# Sheet1.net
KiCad netlist of a schematic drawn in Altium Designer
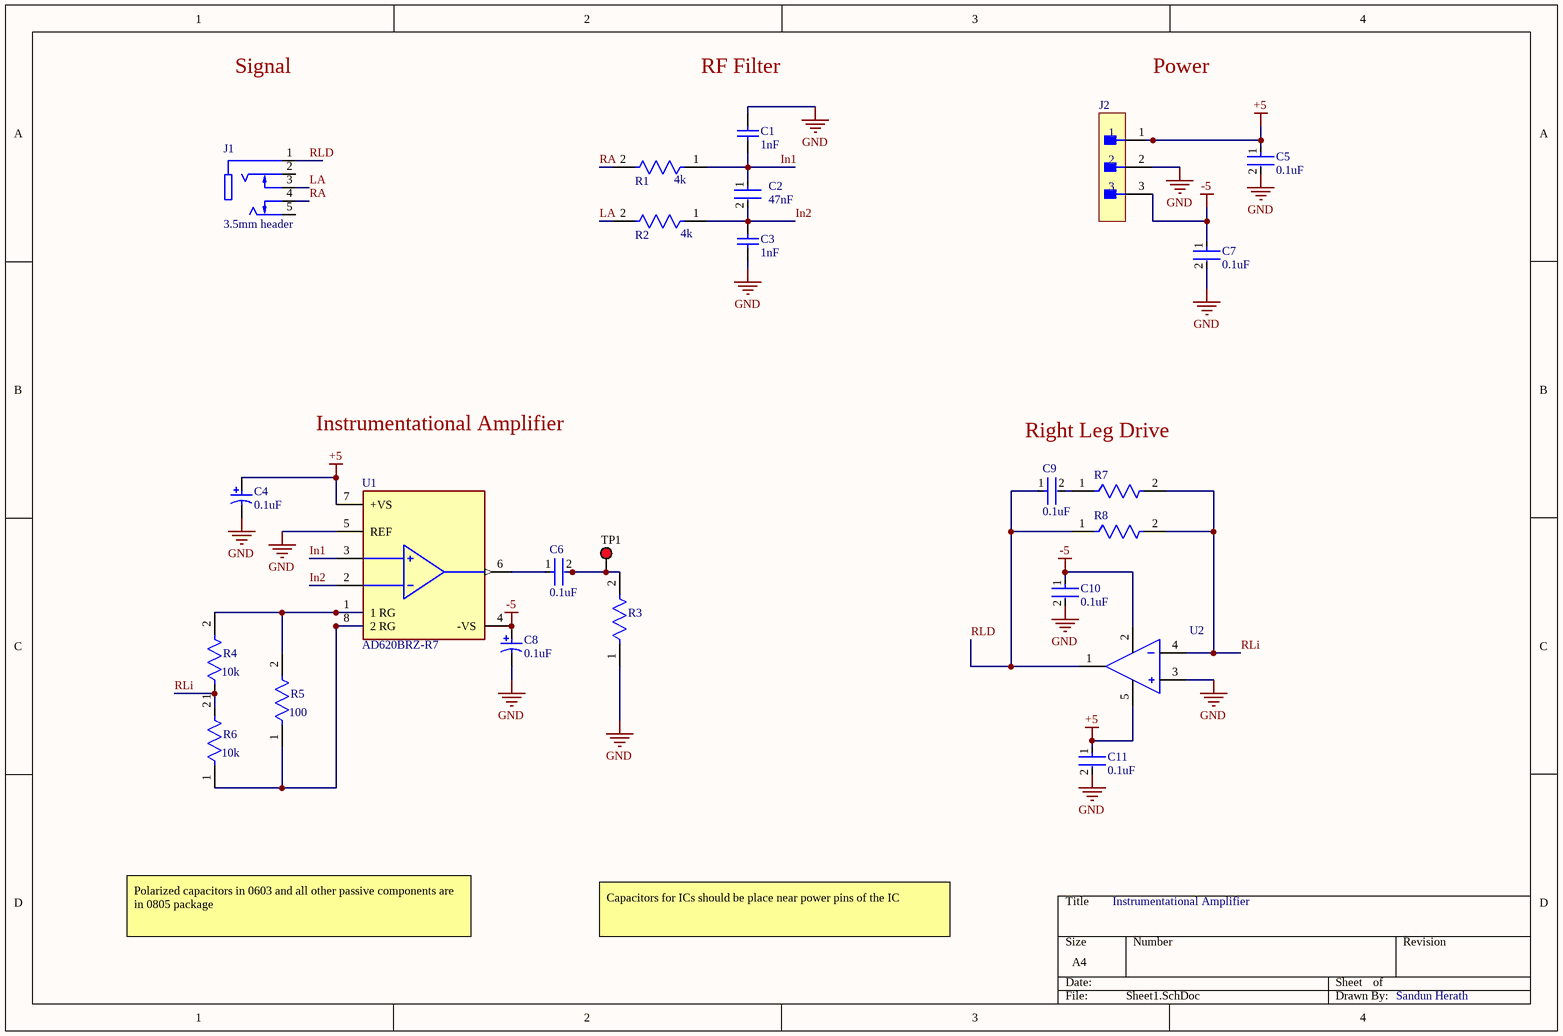
[diagram p0: Sheet1.SchDoc]

(export (version "E")
  (design (tool "Eeschema 10.0.6"))
  (components
    (comp (ref "C1")
      (value "1nF")
      (footprint "CAPC0805(2012)145_L")
      (description "CAP 1nF 50V ±5% 0805 (2012 Metric) Thickness 1.45mm SMD")
      (fields (field (name "TOLERANCE") "Â±5%"))
      (libsource (lib "Altium Content Vault") (part "CAP"))
    )
    (comp (ref "C2")
      (value "47nF")
      (footprint "FP-GRM21B-0_1-IPC_C")
      (fields (field (name "TOLERANCE") "5%"))
      (libsource (lib "Altium Content Vault") (part "b4654b650e69147ec39a6b967a45e02"))
    )
    (comp (ref "C3")
      (value "1nF")
      (footprint "CAPC0805(2012)145_L")
      (description "CAP 1nF 50V ±5% 0805 (2012 Metric) Thickness 1.45mm SMD")
      (fields (field (name "TOLERANCE") "Â±5%"))
      (libsource (lib "Altium Content Vault") (part "CAP"))
    )
    (comp (ref "C4")
      (value "0.1uF")
      (footprint "VISH-TR8-M_L")
      (fields (field (name "TOLERANCE") "±20%") (field (name "MANUFACTURER") "Vishay"))
      (libsource (lib "Altium Content Vault") (part "CAP-P-2"))
    )
    (comp (ref "C5")
      (value "0.1uF")
      (footprint "FP-CL21-IPC_A")
      (description "CL21 Series 0805 100nF 25V ±20% Tolerance X7R Multilayer Ceramic Chip Capacitor, CL21B104MACNNNC")
      (fields (field (name "TOLERANCE") "20%"))
      (libsource (lib "Altium Content Vault") (part "b4654b650e69147ec39a6b967a45e02"))
    )
    (comp (ref "C6")
      (value "0.1uF")
      (footprint "FP-CL21-IPC_A")
      (description "CL21 Series 0805 100nF 25V ±20% Tolerance X7R Multilayer Ceramic Chip Capacitor, CL21B104MACNNNC")
      (fields (field (name "TOLERANCE") "20%"))
      (libsource (lib "Altium Content Vault") (part "b4654b650e69147ec39a6b967a45e02"))
    )
    (comp (ref "C7")
      (value "0.1uF")
      (footprint "FP-CL21-IPC_A")
      (description "CL21 Series 0805 100nF 25V ±20% Tolerance X7R Multilayer Ceramic Chip Capacitor, CL21B104MACNNNC")
      (fields (field (name "TOLERANCE") "20%"))
      (libsource (lib "Altium Content Vault") (part "b4654b650e69147ec39a6b967a45e02"))
    )
    (comp (ref "C8")
      (value "0.1uF")
      (footprint "VISH-TR8-M_L")
      (fields (field (name "TOLERANCE") "±20%") (field (name "MANUFACTURER") "Vishay"))
      (libsource (lib "Altium Content Vault") (part "CAP-P-2"))
    )
    (comp (ref "C9")
      (value "0.1uF")
      (footprint "FP-CL21-IPC_A")
      (description "CL21 Series 0805 100nF 25V ±20% Tolerance X7R Multilayer Ceramic Chip Capacitor, CL21B104MACNNNC")
      (fields (field (name "TOLERANCE") "20%"))
      (libsource (lib "Altium Content Vault") (part "b4654b650e69147ec39a6b967a45e02"))
    )
    (comp (ref "C10")
      (value "0.1uF")
      (footprint "FP-CL21-IPC_A")
      (description "CL21 Series 0805 100nF 25V ±20% Tolerance X7R Multilayer Ceramic Chip Capacitor, CL21B104MACNNNC")
      (fields (field (name "TOLERANCE") "20%"))
      (libsource (lib "Altium Content Vault") (part "b4654b650e69147ec39a6b967a45e02"))
    )
    (comp (ref "C11")
      (value "0.1uF")
      (footprint "FP-CL21-IPC_A")
      (description "CL21 Series 0805 100nF 25V ±20% Tolerance X7R Multilayer Ceramic Chip Capacitor, CL21B104MACNNNC")
      (fields (field (name "TOLERANCE") "20%"))
      (libsource (lib "Altium Content Vault") (part "b4654b650e69147ec39a6b967a45e02"))
    )
    (comp (ref "J1")
      (value "3.5mm header")
      (footprint "SWITCHCRAFT_35RAPC4BH3")
      (fields (field (name "MP") "35RAPC4BH3"))
      (libsource (lib "Schlib1") (part "35RAPC4BH3"))
    )
    (comp (ref "J2")
      (value "M22-2510305")
      (footprint "FP-M22-2510305-MFG")
      (description "M22-2510305 Conn Unshrouded Header M 3 POS 2mm Solder ST Top Entry Thru-Hole Bulk/Loose")
      (libsource (lib "Altium Content Vault") (part "M22-2510305"))
    )
    (comp (ref "R1")
      (value "4k")
      (footprint "FP-ERA6A-IPC_C")
      (description "RES 1K OHM 0.1% 1/8W 0805,  ERA6AEB102V")
      (fields (field (name "TOLERANCE") "0.1%"))
      (libsource (lib "Altium Content Vault") (part "1029c3af85768c4190bb7ad29bc67b5"))
    )
    (comp (ref "R2")
      (value "4k")
      (footprint "FP-ERA6A-IPC_C")
      (description "RES 1K OHM 0.1% 1/8W 0805,  ERA6AEB102V")
      (fields (field (name "TOLERANCE") "0.1%"))
      (libsource (lib "Altium Content Vault") (part "1029c3af85768c4190bb7ad29bc67b5"))
    )
    (comp (ref "R3")
      (value "ERA6AEB102V")
      (footprint "FP-ERA6A-IPC_C")
      (description "RES 1K OHM 0.1% 1/8W 0805")
      (fields (field (name "TOLERANCE") "0.1%"))
      (libsource (lib "Altium Content Vault") (part "1029c3af85768c4190bb7ad29bc67b5"))
    )
    (comp (ref "R4")
      (value "10k")
      (footprint "FP-ERA6A-IPC_C")
      (description "RES 1K OHM 0.1% 1/8W 0805,    ERA6AEB102V")
      (fields (field (name "TOLERANCE") "0.1%"))
      (libsource (lib "Altium Content Vault") (part "1029c3af85768c4190bb7ad29bc67b5"))
    )
    (comp (ref "R5")
      (value "100")
      (footprint "FP-ERA6A-IPC_C")
      (description "RES 1K OHM 0.1% 1/8W 0805,  ERA6AEB102V")
      (fields (field (name "TOLERANCE") "0.1%"))
      (libsource (lib "Altium Content Vault") (part "1029c3af85768c4190bb7ad29bc67b5"))
    )
    (comp (ref "R6")
      (value "10k")
      (footprint "FP-ERA6A-IPC_C")
      (description "RES 1K OHM 0.1% 1/8W 0805,  ERA6AEB102V")
      (fields (field (name "TOLERANCE") "0.1%"))
      (libsource (lib "Altium Content Vault") (part "1029c3af85768c4190bb7ad29bc67b5"))
    )
    (comp (ref "R7")
      (value "ERA6AEB102V")
      (footprint "FP-ERA6A-IPC_C")
      (description "RES 1K OHM 0.1% 1/8W 0805")
      (fields (field (name "TOLERANCE") "0.1%"))
      (libsource (lib "Altium Content Vault") (part "1029c3af85768c4190bb7ad29bc67b5"))
    )
    (comp (ref "R8")
      (value "ERA6AEB102V")
      (footprint "FP-ERA6A-IPC_C")
      (description "RES 1K OHM 0.1% 1/8W 0805")
      (fields (field (name "TOLERANCE") "0.1%"))
      (libsource (lib "Altium Content Vault") (part "1029c3af85768c4190bb7ad29bc67b5"))
    )
    (comp (ref "TP1")
      (value "5010")
      (footprint "KSTN-5010_V")
      (description "Test Point, Red, Through Hole, RoHS, Bulk")
      (fields (field (name "MANUFACTURER") "Keystone"))
      (libsource (lib "Altium Content Vault") (part "TESTPOINT_RED"))
    )
    (comp (ref "U1")
      (value "AD620BRZ-R7")
      (footprint "FP-R-8-IPC_C")
      (description "IC INST AMP 1 CIRCUIT 8SOIC")
      (libsource (lib "Altium Content Vault") (part "34122d4f8c853147fd0c9ba0f33876e"))
    )
    (comp (ref "U2")
      (value "TLV9151IDBVR")
      (footprint "FP-DBV0005A-IPC_A")
      (description "OPAMP")
      (libsource (lib "Altium Content Vault") (part "bdbec92199ce4306a818faf70a0ce6e"))
    )
  )
  (nets
    (net (code "1") (name "+5") (class "Default")
      (node (ref "C11") (pin "1") (pinfunction "1_1") (pintype "passive"))
      (node (ref "C4") (pin "1") (pinfunction "1_1") (pintype "passive"))
      (node (ref "C5") (pin "1") (pinfunction "1_1") (pintype "passive"))
      (node (ref "J2") (pin "1") (pinfunction "1_1") (pintype "passive"))
      (node (ref "U1") (pin "7") (pinfunction "+VS_7") (pintype "power_in"))
      (node (ref "U2") (pin "5") (pinfunction "V+_5") (pintype "power_in"))
    )
    (net (code "2") (name "-5") (class "Default")
      (node (ref "C10") (pin "1") (pinfunction "1_1") (pintype "passive"))
      (node (ref "C7") (pin "1") (pinfunction "1_1") (pintype "passive"))
      (node (ref "C8") (pin "1") (pinfunction "1_1") (pintype "passive"))
      (node (ref "J2") (pin "3") (pinfunction "3_3") (pintype "passive"))
      (node (ref "U1") (pin "4") (pinfunction "-VS_4") (pintype "power_in"))
      (node (ref "U2") (pin "2") (pinfunction "V-_2") (pintype "power_in"))
    )
    (net (code "3") (name "/In1") (class "Default")
      (node (ref "C1") (pin "1") (pinfunction "1_1") (pintype "passive"))
      (node (ref "C2") (pin "1") (pinfunction "1_1") (pintype "passive"))
      (node (ref "R1") (pin "1") (pinfunction "1_1") (pintype "passive"))
      (node (ref "U1") (pin "3") (pinfunction "+IN_3") (pintype "tri_state"))
    )
    (net (code "4") (name "/In2") (class "Default")
      (node (ref "C2") (pin "2") (pinfunction "2_2") (pintype "passive"))
      (node (ref "C3") (pin "2") (pinfunction "2_2") (pintype "passive"))
      (node (ref "R2") (pin "1") (pinfunction "1_1") (pintype "passive"))
      (node (ref "U1") (pin "2") (pinfunction "-IN_2") (pintype "tri_state"))
    )
    (net (code "5") (name "/LA") (class "Default")
      (node (ref "J1") (pin "3") (pinfunction "3_3") (pintype "passive"))
      (node (ref "R2") (pin "2") (pinfunction "2_2") (pintype "passive"))
    )
    (net (code "6") (name "/RA") (class "Default")
      (node (ref "J1") (pin "4") (pinfunction "4_4") (pintype "passive"))
      (node (ref "R1") (pin "2") (pinfunction "2_2") (pintype "passive"))
    )
    (net (code "7") (name "/RLD") (class "Default")
      (node (ref "C9") (pin "1") (pinfunction "1_1") (pintype "passive"))
      (node (ref "J1") (pin "1") (pinfunction "1_1") (pintype "passive"))
      (node (ref "R8") (pin "1") (pinfunction "1_1") (pintype "passive"))
      (node (ref "U2") (pin "1") (pinfunction "OUT_1") (pintype "passive"))
    )
    (net (code "8") (name "/RLi") (class "Default")
      (node (ref "R4") (pin "1") (pinfunction "1_1") (pintype "passive"))
      (node (ref "R6") (pin "2") (pinfunction "2_2") (pintype "passive"))
      (node (ref "R7") (pin "2") (pinfunction "2_2") (pintype "passive"))
      (node (ref "R8") (pin "2") (pinfunction "2_2") (pintype "passive"))
      (node (ref "U2") (pin "4") (pinfunction "IN-_4") (pintype "tri_state"))
    )
    (net (code "9") (name "GND") (class "Default")
      (node (ref "C1") (pin "2") (pinfunction "2_2") (pintype "passive"))
      (node (ref "C10") (pin "2") (pinfunction "2_2") (pintype "passive"))
      (node (ref "C11") (pin "2") (pinfunction "2_2") (pintype "passive"))
      (node (ref "C3") (pin "1") (pinfunction "1_1") (pintype "passive"))
      (node (ref "C4") (pin "2") (pinfunction "2_2") (pintype "passive"))
      (node (ref "C5") (pin "2") (pinfunction "2_2") (pintype "passive"))
      (node (ref "C7") (pin "2") (pinfunction "2_2") (pintype "passive"))
      (node (ref "C8") (pin "2") (pinfunction "2_2") (pintype "passive"))
      (node (ref "J2") (pin "2") (pinfunction "2_2") (pintype "passive"))
      (node (ref "R3") (pin "1") (pinfunction "1_1") (pintype "passive"))
      (node (ref "U1") (pin "5") (pinfunction "REF_5") (pintype "passive"))
      (node (ref "U2") (pin "3") (pinfunction "IN+_3") (pintype "tri_state"))
    )
    (net (code "10") (name "Net-(C6-Pad2)") (class "Default")
      (node (ref "C6") (pin "2") (pinfunction "2_2") (pintype "passive"))
      (node (ref "R3") (pin "2") (pinfunction "2_2") (pintype "passive"))
      (node (ref "TP1") (pin "1") (pinfunction "1_1") (pintype "passive"))
    )
    (net (code "11") (name "Net-(C9-Pad2)") (class "Default")
      (node (ref "C9") (pin "2") (pinfunction "2_2") (pintype "passive"))
      (node (ref "R7") (pin "1") (pinfunction "1_1") (pintype "passive"))
    )
    (net (code "12") (name "Net-(U1-1_RG)") (class "Default")
      (node (ref "R4") (pin "2") (pinfunction "2_2") (pintype "passive"))
      (node (ref "R5") (pin "2") (pinfunction "2_2") (pintype "passive"))
      (node (ref "U1") (pin "1") (pinfunction "1_RG_1") (pintype "passive"))
    )
    (net (code "13") (name "Net-(U1-2_RG)") (class "Default")
      (node (ref "R5") (pin "1") (pinfunction "1_1") (pintype "passive"))
      (node (ref "R6") (pin "1") (pinfunction "1_1") (pintype "passive"))
      (node (ref "U1") (pin "8") (pinfunction "2_RG_8") (pintype "passive"))
    )
    (net (code "14") (name "Net-(U1-OUTPUT)") (class "Default")
      (node (ref "C6") (pin "1") (pinfunction "1_1") (pintype "passive"))
      (node (ref "U1") (pin "6") (pinfunction "OUTPUT_6") (pintype "output"))
    )
    (net (code "15") (name "unconnected-(J1-Pad2)") (class "Default")
      (node (ref "J1") (pin "2") (pinfunction "2_2") (pintype "passive"))
    )
    (net (code "16") (name "unconnected-(J1-Pad5)") (class "Default")
      (node (ref "J1") (pin "5") (pinfunction "5_5") (pintype "passive"))
    )
  )
)
